# usbtinyisp.net
KiCad netlist of a schematic drawn in Altium Designer
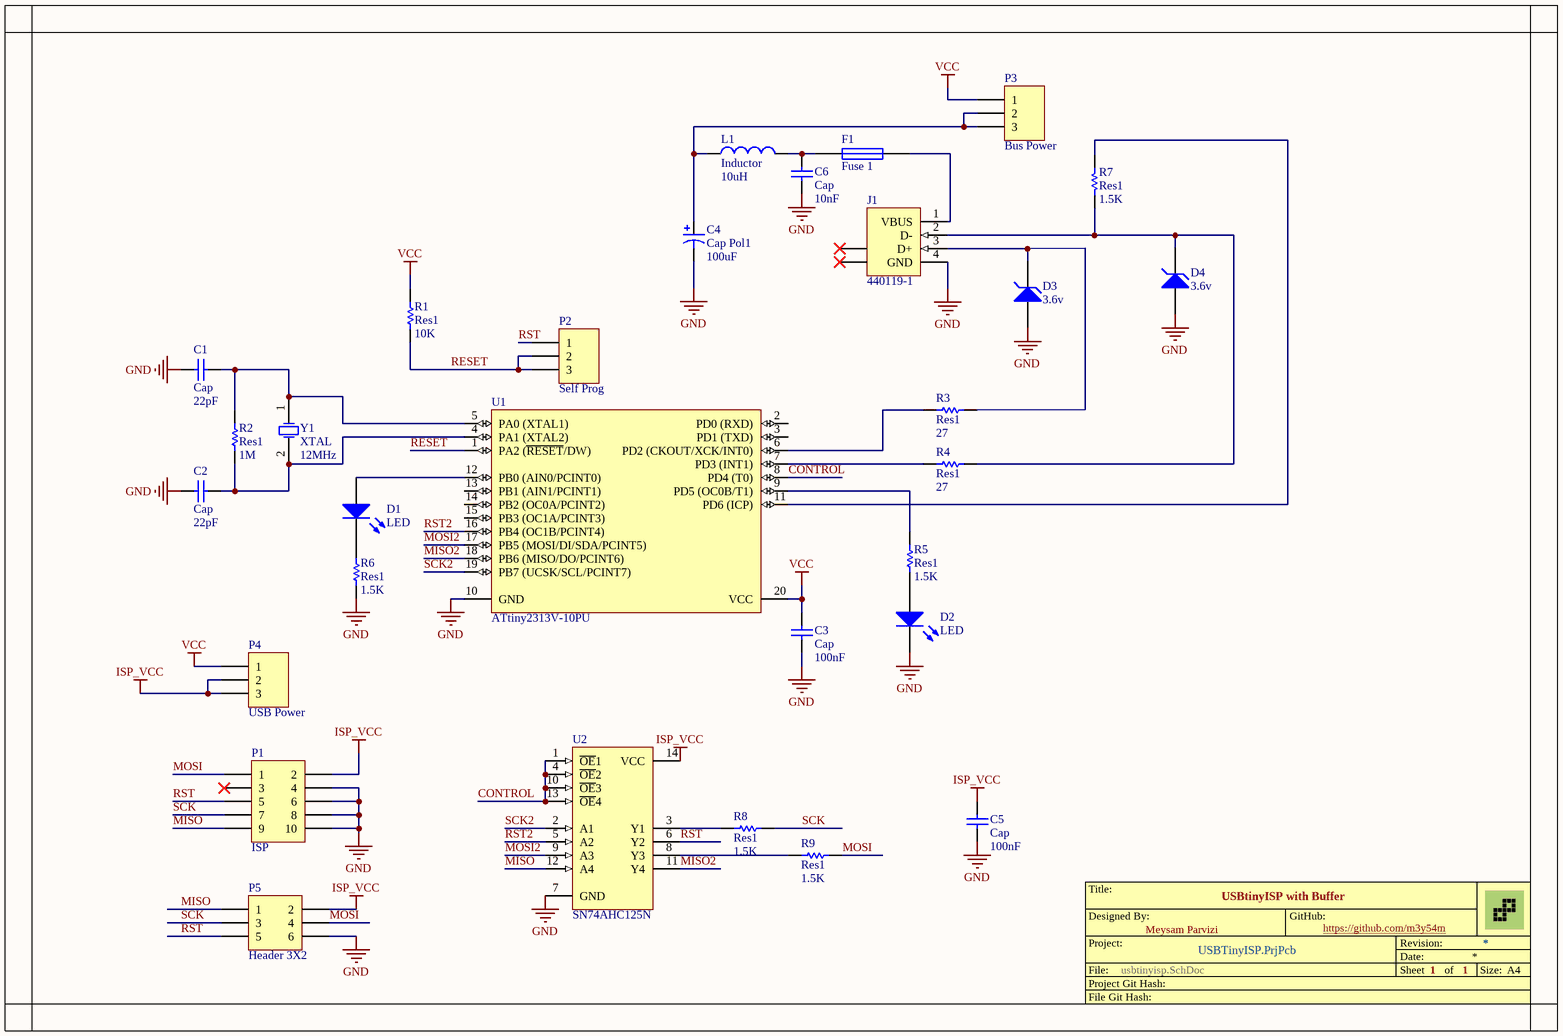
[diagram p0: usbtinyisp.SchDoc]

(export (version "E")
  (design (tool "Eeschema 10.0.6"))
  (components
    (comp (ref "C1")
      (value "Cap")
      (footprint "C1206")
      (description "Capacitor")
      (fields (field (name "ALTIUM_VALUE") "22pF") (field (name "PUBLISHER") "Altium Limited"))
      (libsource (lib "Miscellaneous Devices") (part "Cap"))
    )
    (comp (ref "C2")
      (value "Cap")
      (footprint "C1206")
      (description "Capacitor")
      (fields (field (name "ALTIUM_VALUE") "22pF") (field (name "PUBLISHER") "Altium Limited"))
      (libsource (lib "Miscellaneous Devices") (part "Cap"))
    )
    (comp (ref "C3")
      (value "Cap")
      (footprint "C1206")
      (description "Capacitor")
      (fields (field (name "ALTIUM_VALUE") "100nF") (field (name "PUBLISHER") "Altium Limited"))
      (libsource (lib "Miscellaneous Devices") (part "Cap"))
    )
    (comp (ref "C4")
      (value "Cap Pol1")
      (footprint "CAP-SMD1")
      (description "Polarized Capacitor (Radial)")
      (fields (field (name "ALTIUM_VALUE") "100uF") (field (name "PUBLISHER") "Altium Limited"))
      (libsource (lib "Miscellaneous Devices") (part "Cap Pol1"))
    )
    (comp (ref "C5")
      (value "Cap")
      (footprint "C1206")
      (description "Capacitor")
      (fields (field (name "ALTIUM_VALUE") "100nF") (field (name "PUBLISHER") "Altium Limited"))
      (libsource (lib "Miscellaneous Devices") (part "Cap"))
    )
    (comp (ref "C6")
      (value "Cap")
      (footprint "C1206")
      (description "Capacitor")
      (fields (field (name "ALTIUM_VALUE") "10nF") (field (name "PUBLISHER") "Altium Limited"))
      (libsource (lib "Miscellaneous Devices") (part "Cap"))
    )
    (comp (ref "D1")
      (value "LED")
      (footprint "3.5X2.8X1.9")
      (description "Typical RED GaAs LED")
      (fields (field (name "DESIGNER") "Meysam Parvizi") (field (name "EMAIL") "meysam.parvizi.ir@gmail.com"))
      (libsource (lib "mp") (part "LED"))
    )
    (comp (ref "D2")
      (value "LED")
      (footprint "3.5X2.8X1.9")
      (description "Typical RED GaAs LED")
      (fields (field (name "DESIGNER") "Meysam Parvizi") (field (name "EMAIL") "meysam.parvizi.ir@gmail.com"))
      (libsource (lib "mp") (part "LED"))
    )
    (comp (ref "D3")
      (value "3.6v")
      (footprint "DIODE-S")
      (description "Zener Diode")
      (fields (field (name "PUBLISHER") "Altium Limited"))
      (libsource (lib "Miscellaneous Devices") (part "D Zener"))
    )
    (comp (ref "D4")
      (value "3.6v")
      (footprint "DIODE-S")
      (description "Zener Diode")
      (fields (field (name "PUBLISHER") "Altium Limited"))
      (libsource (lib "Miscellaneous Devices") (part "D Zener"))
    )
    (comp (ref "F1")
      (value "Fuse 1")
      (footprint "C1206")
      (description "Fuse")
      (fields (field (name "PUBLISHER") "Altium Limited"))
      (libsource (lib "Miscellaneous Devices") (part "Fuse 1"))
    )
    (comp (ref "J1")
      (value "440119-1")
      (footprint "440119")
      (description "USB 1.1, Right Angle, Thru-Hole, B Type, Receptacle, 4 Position, Beige")
      (fields (field (name "PUBLISHER") "Altium Limited"))
      (libsource (lib "AMP Serial Bus USB") (part "440119-1"))
    )
    (comp (ref "L1")
      (value "Inductor")
      (footprint "C1206")
      (fields (field (name "ALTIUM_VALUE") "10uH") (field (name "PUBLISHER") "Altium Limited"))
      (libsource (lib "Miscellaneous Devices") (part "Inductor"))
    )
    (comp (ref "P1")
      (value "ISP")
      (footprint "BOX2X5")
      (description "Box, 5-Pin, Dual row")
      (fields (field (name "DESIGNER") "Meysam Parvizi") (field (name "EMAIL") "meysam.parvizi.ir@gmail.com"))
      (libsource (lib "mp") (part "Box 5X2"))
    )
    (comp (ref "P2")
      (value "Self Prog")
      (footprint "HDR1X3")
      (description "Header, 3-Pin")
      (fields (field (name "PUBLISHER") "Altium Limited"))
      (libsource (lib "Miscellaneous Connectors") (part "Header 3"))
    )
    (comp (ref "P3")
      (value "Bus Power")
      (footprint "HDR1X3")
      (description "Header, 3-Pin")
      (fields (field (name "PUBLISHER") "Altium Limited"))
      (libsource (lib "Miscellaneous Connectors") (part "Header 3"))
    )
    (comp (ref "P4")
      (value "USB Power")
      (footprint "HDR1X3")
      (description "Header, 3-Pin")
      (fields (field (name "PUBLISHER") "Altium Limited"))
      (libsource (lib "Miscellaneous Connectors") (part "Header 3"))
    )
    (comp (ref "P5")
      (value "Header 3X2")
      (footprint "HDR2X3")
      (description "Header, 3-Pin, Dual row")
      (fields (field (name "PUBLISHER") "Altium Limited"))
      (libsource (lib "Miscellaneous Connectors") (part "Header 3X2"))
    )
    (comp (ref "R1")
      (value "Res1")
      (footprint "C1206")
      (description "Resistor")
      (fields (field (name "ALTIUM_VALUE") "10K") (field (name "PUBLISHER") "Altium Limited"))
      (libsource (lib "Miscellaneous Devices") (part "Res1"))
    )
    (comp (ref "R2")
      (value "Res1")
      (footprint "C1206")
      (description "Resistor")
      (fields (field (name "ALTIUM_VALUE") "1M") (field (name "PUBLISHER") "Altium Limited"))
      (libsource (lib "Miscellaneous Devices") (part "Res1"))
    )
    (comp (ref "R3")
      (value "Res1")
      (footprint "C1206")
      (description "Resistor")
      (fields (field (name "ALTIUM_VALUE") "27") (field (name "PUBLISHER") "Altium Limited"))
      (libsource (lib "Miscellaneous Devices") (part "Res1"))
    )
    (comp (ref "R4")
      (value "Res1")
      (footprint "C1206")
      (description "Resistor")
      (fields (field (name "ALTIUM_VALUE") "27") (field (name "PUBLISHER") "Altium Limited"))
      (libsource (lib "Miscellaneous Devices") (part "Res1"))
    )
    (comp (ref "R5")
      (value "Res1")
      (footprint "C1206")
      (description "Resistor")
      (fields (field (name "ALTIUM_VALUE") "1.5K") (field (name "PUBLISHER") "Altium Limited"))
      (libsource (lib "Miscellaneous Devices") (part "Res1"))
    )
    (comp (ref "R6")
      (value "Res1")
      (footprint "C1206")
      (description "Resistor")
      (fields (field (name "ALTIUM_VALUE") "1.5K") (field (name "PUBLISHER") "Altium Limited"))
      (libsource (lib "Miscellaneous Devices") (part "Res1"))
    )
    (comp (ref "R7")
      (value "Res1")
      (footprint "C1206")
      (description "Resistor")
      (fields (field (name "ALTIUM_VALUE") "1.5K") (field (name "PUBLISHER") "Altium Limited"))
      (libsource (lib "Miscellaneous Devices") (part "Res1"))
    )
    (comp (ref "R8")
      (value "Res1")
      (footprint "C1206")
      (description "Resistor")
      (fields (field (name "ALTIUM_VALUE") "1.5K") (field (name "PUBLISHER") "Altium Limited"))
      (libsource (lib "Miscellaneous Devices") (part "Res1"))
    )
    (comp (ref "R9")
      (value "Res1")
      (footprint "C1206")
      (description "Resistor")
      (fields (field (name "ALTIUM_VALUE") "1.5K") (field (name "PUBLISHER") "Altium Limited"))
      (libsource (lib "Miscellaneous Devices") (part "Res1"))
    )
    (comp (ref "U1")
      (value "ATtiny2313V-10PU")
      (footprint "DIP20")
      (fields (field (name "PUBLISHER") "Altium Limited"))
      (libsource (lib "Atmel Microcontroller 8-Bit tinyAVR") (part "ATtiny2313V-10PU"))
    )
    (comp (ref "U2")
      (value "SN74AHC125N")
      (footprint "DIP14")
      (description "Quadruple Bus Buffer Gate with 3-State Outputs")
      (fields (field (name "PUBLISHER") "Altium Limited"))
      (libsource (lib "TI Logic Buffer Line Driver") (part "SN74AHC125N"))
    )
    (comp (ref "Y1")
      (value "XTAL")
      (footprint "XTAL")
      (description "Crystal Oscillator")
      (fields
        (field (name "ALTIUM_VALUE") "12MHz")
        (field (name "DESIGNER") "Meysam Parvizi")
        (field (name "EMAIL") "meysam.parvizi.ir@gmail.com")
      )
      (libsource (lib "mp") (part "XTAL"))
    )
  )
  (nets
    (net (code "1") (name "/CONTROL") (class "Default")
      (node (ref "U1") (pin "8") (pinfunction "PD4_(T0)_8") (pintype "bidirectional"))
      (node (ref "U2") (pin "1") (pinfunction "~{OE}1_1") (pintype "input"))
      (node (ref "U2") (pin "10") (pinfunction "~{OE}3_10") (pintype "input"))
      (node (ref "U2") (pin "13") (pinfunction "~{OE}4_13") (pintype "input"))
      (node (ref "U2") (pin "4") (pinfunction "~{OE}2_4") (pintype "input"))
    )
    (net (code "2") (name "/MISO") (class "Default")
      (node (ref "P1") (pin "9") (pinfunction "9_9") (pintype "passive"))
      (node (ref "P5") (pin "1") (pinfunction "1_1") (pintype "passive"))
      (node (ref "U2") (pin "12") (pinfunction "A4_12") (pintype "input"))
    )
    (net (code "3") (name "/MISO2") (class "Default")
      (node (ref "U1") (pin "18") (pinfunction "PB6_(MISO/DO/PCINT6)_18") (pintype "bidirectional"))
      (node (ref "U2") (pin "11") (pinfunction "Y4_11") (pintype "tri_state"))
    )
    (net (code "4") (name "/MOSI") (class "Default")
      (node (ref "P1") (pin "1") (pinfunction "1_1") (pintype "passive"))
      (node (ref "P5") (pin "4") (pinfunction "4_4") (pintype "passive"))
      (node (ref "R9") (pin "2") (pinfunction "2_2") (pintype "passive"))
    )
    (net (code "5") (name "/MOSI2") (class "Default")
      (node (ref "U1") (pin "17") (pinfunction "PB5_(MOSI/DI/SDA/PCINT5)_17") (pintype "bidirectional"))
      (node (ref "U2") (pin "9") (pinfunction "A3_9") (pintype "input"))
    )
    (net (code "6") (name "/RESET") (class "Default")
      (node (ref "P2") (pin "2") (pinfunction "2_2") (pintype "passive"))
      (node (ref "P2") (pin "3") (pinfunction "3_3") (pintype "passive"))
      (node (ref "R1") (pin "1") (pinfunction "1_1") (pintype "passive"))
      (node (ref "U1") (pin "1") (pinfunction "PA2_(~{RESET}/DW)_1") (pintype "bidirectional"))
    )
    (net (code "7") (name "/RST") (class "Default")
      (node (ref "P1") (pin "5") (pinfunction "5_5") (pintype "passive"))
      (node (ref "P2") (pin "1") (pinfunction "1_1") (pintype "passive"))
      (node (ref "P5") (pin "5") (pinfunction "5_5") (pintype "passive"))
      (node (ref "U2") (pin "6") (pinfunction "Y2_6") (pintype "tri_state"))
    )
    (net (code "8") (name "/RST2") (class "Default")
      (node (ref "U1") (pin "16") (pinfunction "PB4_(OC1B/PCINT4)_16") (pintype "bidirectional"))
      (node (ref "U2") (pin "5") (pinfunction "A2_5") (pintype "input"))
    )
    (net (code "9") (name "/SCK") (class "Default")
      (node (ref "P1") (pin "7") (pinfunction "7_7") (pintype "passive"))
      (node (ref "P5") (pin "3") (pinfunction "3_3") (pintype "passive"))
      (node (ref "R8") (pin "2") (pinfunction "2_2") (pintype "passive"))
    )
    (net (code "10") (name "/SCK2") (class "Default")
      (node (ref "U1") (pin "19") (pinfunction "PB7_(UCSK/SCL/PCINT7)_19") (pintype "bidirectional"))
      (node (ref "U2") (pin "2") (pinfunction "A1_2") (pintype "input"))
    )
    (net (code "11") (name "GND") (class "Default")
      (node (ref "C1") (pin "1") (pinfunction "1_1") (pintype "passive"))
      (node (ref "C2") (pin "1") (pinfunction "1_1") (pintype "passive"))
      (node (ref "C3") (pin "1") (pinfunction "1_1") (pintype "passive"))
      (node (ref "C4") (pin "2") (pinfunction "2_2") (pintype "passive"))
      (node (ref "C5") (pin "1") (pinfunction "1_1") (pintype "passive"))
      (node (ref "C6") (pin "1") (pinfunction "1_1") (pintype "passive"))
      (node (ref "D2") (pin "2") (pinfunction "K_2") (pintype "passive"))
      (node (ref "D3") (pin "1") (pinfunction "A_1") (pintype "passive"))
      (node (ref "D4") (pin "1") (pinfunction "A_1") (pintype "passive"))
      (node (ref "J1") (pin "4") (pinfunction "GND_4") (pintype "power_in"))
      (node (ref "P1") (pin "10") (pinfunction "10_10") (pintype "passive"))
      (node (ref "P1") (pin "4") (pinfunction "4_4") (pintype "passive"))
      (node (ref "P1") (pin "6") (pinfunction "6_6") (pintype "passive"))
      (node (ref "P1") (pin "8") (pinfunction "8_8") (pintype "passive"))
      (node (ref "P5") (pin "6") (pinfunction "6_6") (pintype "passive"))
      (node (ref "R6") (pin "2") (pinfunction "2_2") (pintype "passive"))
      (node (ref "U1") (pin "10") (pinfunction "GND_10") (pintype "power_in"))
      (node (ref "U2") (pin "7") (pinfunction "GND_7") (pintype "power_in"))
    )
    (net (code "12") (name "ISP_VCC") (class "Default")
      (node (ref "C5") (pin "2") (pinfunction "2_2") (pintype "passive"))
      (node (ref "P1") (pin "2") (pinfunction "2_2") (pintype "passive"))
      (node (ref "P4") (pin "2") (pinfunction "2_2") (pintype "passive"))
      (node (ref "P4") (pin "3") (pinfunction "3_3") (pintype "passive"))
      (node (ref "P5") (pin "2") (pinfunction "2_2") (pintype "passive"))
      (node (ref "U2") (pin "14") (pinfunction "VCC_14") (pintype "power_in"))
    )
    (net (code "13") (name "Net-(C4-Pad1)") (class "Default")
      (node (ref "C4") (pin "1") (pinfunction "1_1") (pintype "passive"))
      (node (ref "L1") (pin "1") (pinfunction "1_1") (pintype "passive"))
      (node (ref "P3") (pin "2") (pinfunction "2_2") (pintype "passive"))
      (node (ref "P3") (pin "3") (pinfunction "3_3") (pintype "passive"))
    )
    (net (code "14") (name "Net-(C6-Pad2)") (class "Default")
      (node (ref "C6") (pin "2") (pinfunction "2_2") (pintype "passive"))
      (node (ref "F1") (pin "1") (pinfunction "1_1") (pintype "passive"))
      (node (ref "L1") (pin "2") (pinfunction "2_2") (pintype "passive"))
    )
    (net (code "15") (name "Net-(D1-A)") (class "Default")
      (node (ref "D1") (pin "1") (pinfunction "A_1") (pintype "passive"))
      (node (ref "U1") (pin "12") (pinfunction "PB0_(AIN0/PCINT0)_12") (pintype "bidirectional"))
    )
    (net (code "16") (name "Net-(D1-K)") (class "Default")
      (node (ref "D1") (pin "2") (pinfunction "K_2") (pintype "passive"))
      (node (ref "R6") (pin "1") (pinfunction "1_1") (pintype "passive"))
    )
    (net (code "17") (name "Net-(D2-A)") (class "Default")
      (node (ref "D2") (pin "1") (pinfunction "A_1") (pintype "passive"))
      (node (ref "R5") (pin "2") (pinfunction "2_2") (pintype "passive"))
    )
    (net (code "18") (name "Net-(D3-K)") (class "Default")
      (node (ref "D3") (pin "2") (pinfunction "K_2") (pintype "passive"))
      (node (ref "J1") (pin "3") (pinfunction "D+_3") (pintype "input"))
      (node (ref "R3") (pin "1") (pinfunction "1_1") (pintype "passive"))
    )
    (net (code "19") (name "Net-(D4-K)") (class "Default")
      (node (ref "D4") (pin "2") (pinfunction "K_2") (pintype "passive"))
      (node (ref "J1") (pin "2") (pinfunction "D-_2") (pintype "input"))
      (node (ref "R4") (pin "1") (pinfunction "1_1") (pintype "passive"))
      (node (ref "R7") (pin "1") (pinfunction "1_1") (pintype "passive"))
    )
    (net (code "20") (name "Net-(J1-VBUS)") (class "Default")
      (node (ref "F1") (pin "2") (pinfunction "2_2") (pintype "passive"))
      (node (ref "J1") (pin "1") (pinfunction "VBUS_1") (pintype "power_in"))
    )
    (net (code "21") (name "Net-(U1-PA0_(XTAL1))") (class "Default")
      (node (ref "C1") (pin "2") (pinfunction "2_2") (pintype "passive"))
      (node (ref "R2") (pin "2") (pinfunction "2_2") (pintype "passive"))
      (node (ref "U1") (pin "5") (pinfunction "PA0_(XTAL1)_5") (pintype "bidirectional"))
      (node (ref "Y1") (pin "1") (pinfunction "OSC1_1") (pintype "passive"))
    )
    (net (code "22") (name "Net-(U1-PA1_(XTAL2))") (class "Default")
      (node (ref "C2") (pin "2") (pinfunction "2_2") (pintype "passive"))
      (node (ref "R2") (pin "1") (pinfunction "1_1") (pintype "passive"))
      (node (ref "U1") (pin "4") (pinfunction "PA1_(XTAL2)_4") (pintype "bidirectional"))
      (node (ref "Y1") (pin "2") (pinfunction "OSC2_2") (pintype "passive"))
    )
    (net (code "23") (name "Net-(U1-PD2_(CKOUT{slash}XCK{slash}INT0))") (class "Default")
      (node (ref "R3") (pin "2") (pinfunction "2_2") (pintype "passive"))
      (node (ref "U1") (pin "6") (pinfunction "PD2_(CKOUT/XCK/INT0)_6") (pintype "bidirectional"))
    )
    (net (code "24") (name "Net-(U1-PD3_(INT1))") (class "Default")
      (node (ref "R4") (pin "2") (pinfunction "2_2") (pintype "passive"))
      (node (ref "U1") (pin "7") (pinfunction "PD3_(INT1)_7") (pintype "bidirectional"))
    )
    (net (code "25") (name "Net-(U1-PD5_(OC0B{slash}T1))") (class "Default")
      (node (ref "R5") (pin "1") (pinfunction "1_1") (pintype "passive"))
      (node (ref "U1") (pin "9") (pinfunction "PD5_(OC0B/T1)_9") (pintype "bidirectional"))
    )
    (net (code "26") (name "Net-(U1-PD6_(ICP))") (class "Default")
      (node (ref "R7") (pin "2") (pinfunction "2_2") (pintype "passive"))
      (node (ref "U1") (pin "11") (pinfunction "PD6_(ICP)_11") (pintype "bidirectional"))
    )
    (net (code "27") (name "Net-(U2-Y1)") (class "Default")
      (node (ref "R8") (pin "1") (pinfunction "1_1") (pintype "passive"))
      (node (ref "U2") (pin "3") (pinfunction "Y1_3") (pintype "tri_state"))
    )
    (net (code "28") (name "Net-(U2-Y3)") (class "Default")
      (node (ref "R9") (pin "1") (pinfunction "1_1") (pintype "passive"))
      (node (ref "U2") (pin "8") (pinfunction "Y3_8") (pintype "tri_state"))
    )
    (net (code "29") (name "VCC") (class "Default")
      (node (ref "C3") (pin "2") (pinfunction "2_2") (pintype "passive"))
      (node (ref "P3") (pin "1") (pinfunction "1_1") (pintype "passive"))
      (node (ref "P4") (pin "1") (pinfunction "1_1") (pintype "passive"))
      (node (ref "R1") (pin "2") (pinfunction "2_2") (pintype "passive"))
      (node (ref "U1") (pin "20") (pinfunction "VCC_20") (pintype "power_in"))
    )
    (net (code "30") (name "unconnected-(J1-SHLD-Pad5)") (class "Default")
      (node (ref "J1") (pin "5") (pinfunction "SHLD_5") (pintype "passive+no_connect"))
    )
    (net (code "31") (name "unconnected-(J1-SHLD-Pad6)") (class "Default")
      (node (ref "J1") (pin "6") (pinfunction "SHLD_6") (pintype "passive+no_connect"))
    )
    (net (code "32") (name "unconnected-(P1-Pad3)") (class "Default")
      (node (ref "P1") (pin "3") (pinfunction "3_3") (pintype "passive+no_connect"))
    )
    (net (code "33") (name "unconnected-(U1-PB1_(AIN1{slash}PCINT1)-Pad13)") (class "Default")
      (node (ref "U1") (pin "13") (pinfunction "PB1_(AIN1/PCINT1)_13") (pintype "bidirectional"))
    )
    (net (code "34") (name "unconnected-(U1-PB2_(OC0A{slash}PCINT2)-Pad14)") (class "Default")
      (node (ref "U1") (pin "14") (pinfunction "PB2_(OC0A/PCINT2)_14") (pintype "bidirectional"))
    )
    (net (code "35") (name "unconnected-(U1-PB3_(OC1A{slash}PCINT3)-Pad15)") (class "Default")
      (node (ref "U1") (pin "15") (pinfunction "PB3_(OC1A/PCINT3)_15") (pintype "bidirectional"))
    )
    (net (code "36") (name "unconnected-(U1-PD0_(RXD)-Pad2)") (class "Default")
      (node (ref "U1") (pin "2") (pinfunction "PD0_(RXD)_2") (pintype "bidirectional"))
    )
    (net (code "37") (name "unconnected-(U1-PD1_(TXD)-Pad3)") (class "Default")
      (node (ref "U1") (pin "3") (pinfunction "PD1_(TXD)_3") (pintype "bidirectional"))
    )
  )
)
